# led-cpu.net
KiCad netlist of a schematic drawn in EAGLE
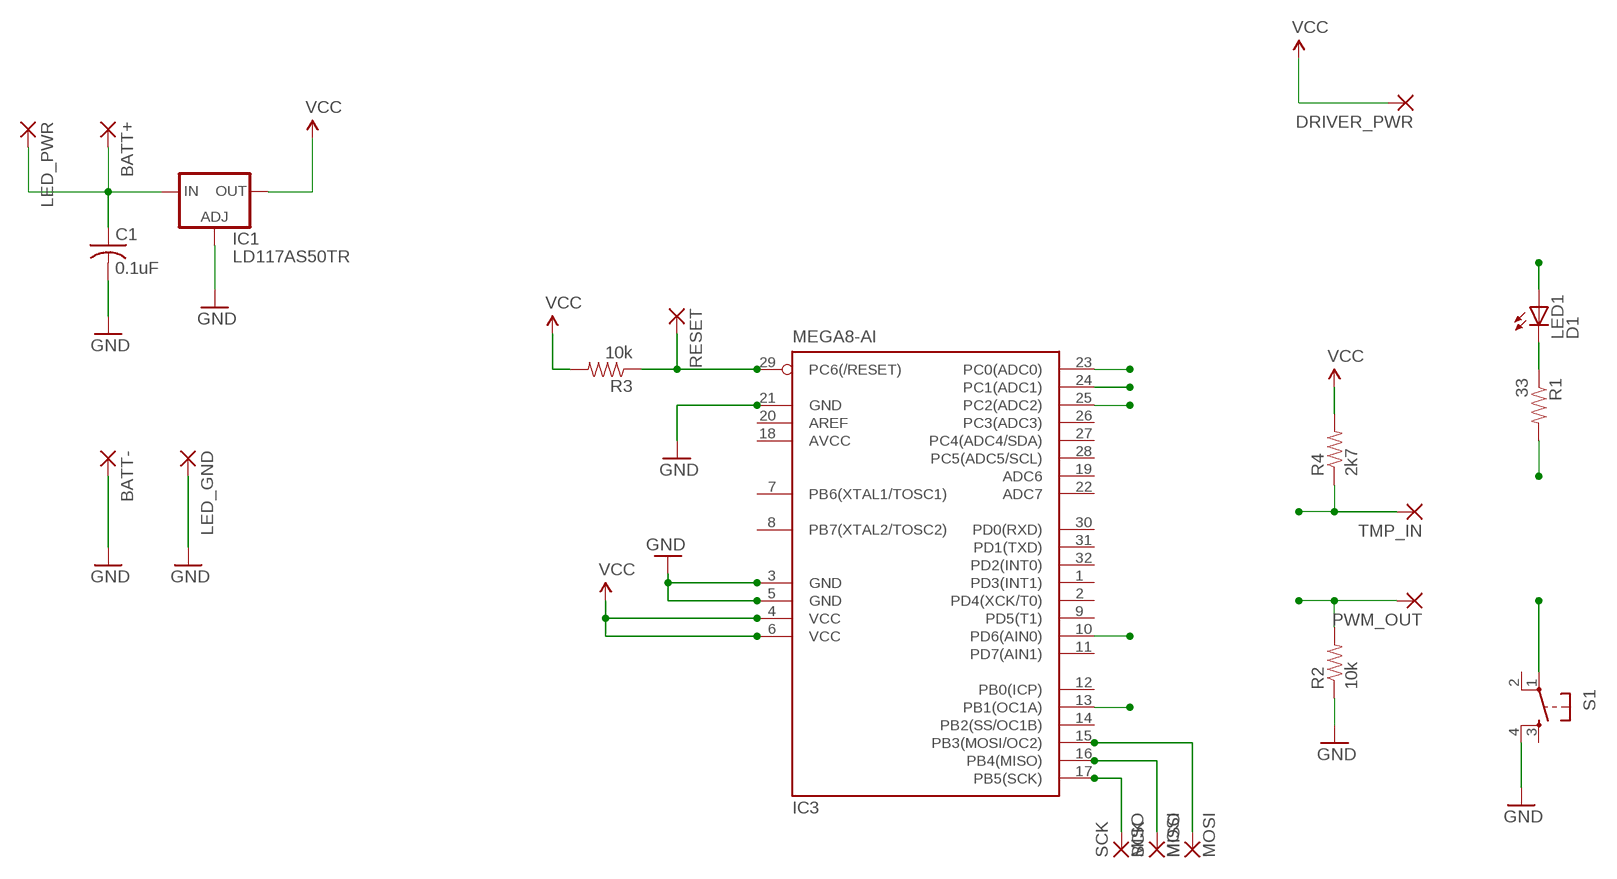
[diagram p0: schematic, sheet 1]

(export (version "E")
  (design (tool "Eeschema 10.0.6"))
  (components
    (comp (ref "BATT+")
      (value "SMD5")
      (footprint "eagle-import:SMD2,54-5,08")
      (libsource (lib "eagle-import") (part "SMD5"))
    )
    (comp (ref "BATT-")
      (value "SMD5")
      (footprint "eagle-import:SMD2,54-5,08")
      (libsource (lib "eagle-import") (part "SMD5"))
    )
    (comp (ref "C1")
      (value "0.1uF")
      (footprint "eagle-import:C0805")
      (libsource (lib "eagle-import") (part "C-USC0805"))
    )
    (comp (ref "DRIVER_PWR")
      (value "WIREPADSMD1,27-254")
      (footprint "eagle-import:SMD1,27-2,54")
      (libsource (lib "eagle-import") (part "WIREPADSMD1,27-254"))
    )
    (comp (ref "IC1")
      (value "LD117AS50TR")
      (footprint "eagle-import:SOT223")
      (libsource (lib "eagle-import") (part "LD117A?S50TR"))
    )
    (comp (ref "IC3")
      (value "MEGA8-AI")
      (footprint "eagle-import:TQFP32-08")
      (fields (field (name "MPN") "ATMEGA8-16AU"))
      (libsource (lib "eagle-import") (part "MEGA8-AI"))
    )
    (comp (ref "LED1")
      (value "D1")
      (footprint "eagle-import:CHIPLED_1206")
      (libsource (lib "eagle-import") (part "LEDCHIPLED_1206"))
    )
    (comp (ref "LED_GND")
      (value "WIREPADSMD1,27-254")
      (footprint "eagle-import:SMD1,27-2,54")
      (libsource (lib "eagle-import") (part "WIREPADSMD1,27-254"))
    )
    (comp (ref "LED_PWR")
      (value "WIREPADSMD1,27-254")
      (footprint "eagle-import:SMD1,27-2,54")
      (libsource (lib "eagle-import") (part "WIREPADSMD1,27-254"))
    )
    (comp (ref "MISO")
      (value "MISO")
      (footprint "eagle-import:SMD1,27-2,54")
      (libsource (lib "eagle-import") (part "SMD2"))
    )
    (comp (ref "MOSI")
      (value "MOSI")
      (footprint "eagle-import:SMD1,27-2,54")
      (libsource (lib "eagle-import") (part "SMD2"))
    )
    (comp (ref "PWM_OUT")
      (value "WIREPADSMD1,27-254")
      (footprint "eagle-import:SMD1,27-2,54")
      (libsource (lib "eagle-import") (part "WIREPADSMD1,27-254"))
    )
    (comp (ref "R1")
      (value "33")
      (footprint "eagle-import:0603-RES")
      (libsource (lib "eagle-import") (part "RESISTOR0603-RES"))
    )
    (comp (ref "R2")
      (value "10k")
      (footprint "eagle-import:0603-RES")
      (libsource (lib "eagle-import") (part "RESISTOR0603-RES"))
    )
    (comp (ref "R3")
      (value "10k")
      (footprint "eagle-import:0603-RES")
      (libsource (lib "eagle-import") (part "RESISTOR0603-RES"))
    )
    (comp (ref "R4")
      (value "2k7")
      (footprint "eagle-import:0603-RES")
      (libsource (lib "eagle-import") (part "RESISTOR0603-RES"))
    )
    (comp (ref "RESET")
      (value "SMD2")
      (footprint "eagle-import:SMD1,27-2,54")
      (libsource (lib "eagle-import") (part "SMD2"))
    )
    (comp (ref "S1")
      (value "TAC_SWITCHPTH")
      (footprint "eagle-import:TACTILE-PTH")
      (libsource (lib "eagle-import") (part "TAC_SWITCHPTH"))
    )
    (comp (ref "SCK")
      (value "SCK")
      (footprint "eagle-import:SMD1,27-2,54")
      (libsource (lib "eagle-import") (part "SMD2"))
    )
    (comp (ref "TMP_IN")
      (value "WIREPADSMD1,27-254")
      (footprint "eagle-import:SMD1,27-2,54")
      (libsource (lib "eagle-import") (part "WIREPADSMD1,27-254"))
    )
  )
  (nets
    (net (code "1") (name "/AVCC") (class "Default")
      (node (ref "IC3") (pin "18") (pinfunction "AVCC_18") (pintype "power_in"))
    )
    (net (code "2") (name "/IND_LED_A") (class "Default")
      (node (ref "IC3") (pin "25") (pinfunction "PC2(ADC2)_25") (pintype "bidirectional"))
      (node (ref "LED1") (pin "A") (pinfunction "A_A") (pintype "passive"))
    )
    (net (code "3") (name "/IND_LED_B") (class "Default")
      (node (ref "IC3") (pin "13") (pinfunction "PB1(OC1A)_13") (pintype "bidirectional"))
      (node (ref "R1") (pin "2") (pinfunction "2_2") (pintype "passive"))
    )
    (net (code "4") (name "/PWM_OUT") (class "Default")
      (node (ref "IC3") (pin "10") (pinfunction "PD6(AIN0)_10") (pintype "bidirectional"))
      (node (ref "PWM_OUT") (pin "1") (pinfunction "P_1") (pintype "passive"))
      (node (ref "R2") (pin "2") (pinfunction "2_2") (pintype "passive"))
    )
    (net (code "5") (name "/PWR_SW") (class "Default")
      (node (ref "IC3") (pin "24") (pinfunction "PC1(ADC1)_24") (pintype "bidirectional"))
      (node (ref "S1") (pin "1") (pinfunction "1_1") (pintype "passive"))
    )
    (net (code "6") (name "/TMP_IN") (class "Default")
      (node (ref "IC3") (pin "23") (pinfunction "PC0(ADC0)_23") (pintype "bidirectional"))
      (node (ref "R4") (pin "1") (pinfunction "1_1") (pintype "passive"))
      (node (ref "TMP_IN") (pin "1") (pinfunction "P_1") (pintype "passive"))
    )
    (net (code "7") (name "GND") (class "Default")
      (node (ref "BATT-") (pin "1") (pinfunction "P_1") (pintype "passive"))
      (node (ref "C1") (pin "2") (pinfunction "2_2") (pintype "passive"))
      (node (ref "IC1") (pin "1") (pinfunction "ADJ_1") (pintype "input"))
      (node (ref "IC3") (pin "21") (pinfunction "GND_21") (pintype "power_in"))
      (node (ref "IC3") (pin "3") (pinfunction "GND_3") (pintype "power_in"))
      (node (ref "IC3") (pin "5") (pinfunction "GND_5") (pintype "power_in"))
      (node (ref "LED_GND") (pin "1") (pinfunction "P_1") (pintype "passive"))
      (node (ref "R2") (pin "1") (pinfunction "1_1") (pintype "passive"))
      (node (ref "S1") (pin "4") (pinfunction "4_4") (pintype "passive"))
    )
    (net (code "8") (name "Net-(BATT+-P)") (class "Default")
      (node (ref "BATT+") (pin "1") (pinfunction "P_1") (pintype "passive"))
      (node (ref "C1") (pin "1") (pinfunction "1_1") (pintype "passive"))
      (node (ref "IC1") (pin "3") (pinfunction "IN_3") (pintype "input"))
      (node (ref "LED_PWR") (pin "1") (pinfunction "P_1") (pintype "passive"))
    )
    (net (code "9") (name "Net-(IC3-PB3(MOSI{slash}OC2))") (class "Default")
      (node (ref "IC3") (pin "15") (pinfunction "PB3(MOSI/OC2)_15") (pintype "bidirectional"))
      (node (ref "MOSI") (pin "1") (pinfunction "P_1") (pintype "passive"))
    )
    (net (code "10") (name "Net-(IC3-PB4(MISO))") (class "Default")
      (node (ref "IC3") (pin "16") (pinfunction "PB4(MISO)_16") (pintype "bidirectional"))
      (node (ref "MISO") (pin "1") (pinfunction "P_1") (pintype "passive"))
    )
    (net (code "11") (name "Net-(IC3-PB5(SCK))") (class "Default")
      (node (ref "IC3") (pin "17") (pinfunction "PB5(SCK)_17") (pintype "bidirectional"))
      (node (ref "SCK") (pin "1") (pinfunction "P_1") (pintype "passive"))
    )
    (net (code "12") (name "Net-(IC3-PC6({slash}RESET))") (class "Default")
      (node (ref "IC3") (pin "29") (pinfunction "PC6(/RESET)_29") (pintype "bidirectional"))
      (node (ref "R3") (pin "1") (pinfunction "1_1") (pintype "passive"))
      (node (ref "RESET") (pin "1") (pinfunction "P_1") (pintype "passive"))
    )
    (net (code "13") (name "Net-(LED1-PadC)") (class "Default")
      (node (ref "LED1") (pin "C") (pinfunction "C_C") (pintype "passive"))
      (node (ref "R1") (pin "1") (pinfunction "1_1") (pintype "passive"))
    )
    (net (code "14") (name "VCC") (class "Default")
      (node (ref "DRIVER_PWR") (pin "1") (pinfunction "P_1") (pintype "passive"))
      (node (ref "IC1") (pin "4") (pinfunction "OUT_4") (pintype "passive"))
      (node (ref "IC3") (pin "4") (pinfunction "VCC_4") (pintype "power_in"))
      (node (ref "IC3") (pin "6") (pinfunction "VCC_6") (pintype "power_in"))
      (node (ref "R3") (pin "2") (pinfunction "2_2") (pintype "passive"))
      (node (ref "R4") (pin "2") (pinfunction "2_2") (pintype "passive"))
    )
    (net (code "15") (name "unconnected-(IC3-ADC6-Pad19)") (class "Default")
      (node (ref "IC3") (pin "19") (pinfunction "ADC6_19") (pintype "bidirectional"))
    )
    (net (code "16") (name "unconnected-(IC3-ADC7-Pad22)") (class "Default")
      (node (ref "IC3") (pin "22") (pinfunction "ADC7_22") (pintype "bidirectional"))
    )
    (net (code "17") (name "unconnected-(IC3-AREF-Pad20)") (class "Default")
      (node (ref "IC3") (pin "20") (pinfunction "AREF_20") (pintype "passive"))
    )
    (net (code "18") (name "unconnected-(IC3-PB0(ICP)-Pad12)") (class "Default")
      (node (ref "IC3") (pin "12") (pinfunction "PB0(ICP)_12") (pintype "bidirectional"))
    )
    (net (code "19") (name "unconnected-(IC3-PB2(SS{slash}OC1B)-Pad14)") (class "Default")
      (node (ref "IC3") (pin "14") (pinfunction "PB2(SS/OC1B)_14") (pintype "bidirectional"))
    )
    (net (code "20") (name "unconnected-(IC3-PB6(XTAL1{slash}TOSC1)-Pad7)") (class "Default")
      (node (ref "IC3") (pin "7") (pinfunction "PB6(XTAL1/TOSC1)_7") (pintype "bidirectional"))
    )
    (net (code "21") (name "unconnected-(IC3-PB7(XTAL2{slash}TOSC2)-Pad8)") (class "Default")
      (node (ref "IC3") (pin "8") (pinfunction "PB7(XTAL2/TOSC2)_8") (pintype "bidirectional"))
    )
    (net (code "22") (name "unconnected-(IC3-PC3(ADC3)-Pad26)") (class "Default")
      (node (ref "IC3") (pin "26") (pinfunction "PC3(ADC3)_26") (pintype "bidirectional"))
    )
    (net (code "23") (name "unconnected-(IC3-PC4(ADC4{slash}SDA)-Pad27)") (class "Default")
      (node (ref "IC3") (pin "27") (pinfunction "PC4(ADC4/SDA)_27") (pintype "bidirectional"))
    )
    (net (code "24") (name "unconnected-(IC3-PC5(ADC5{slash}SCL)-Pad28)") (class "Default")
      (node (ref "IC3") (pin "28") (pinfunction "PC5(ADC5/SCL)_28") (pintype "bidirectional"))
    )
    (net (code "25") (name "unconnected-(IC3-PD0(RXD)-Pad30)") (class "Default")
      (node (ref "IC3") (pin "30") (pinfunction "PD0(RXD)_30") (pintype "bidirectional"))
    )
    (net (code "26") (name "unconnected-(IC3-PD1(TXD)-Pad31)") (class "Default")
      (node (ref "IC3") (pin "31") (pinfunction "PD1(TXD)_31") (pintype "bidirectional"))
    )
    (net (code "27") (name "unconnected-(IC3-PD2(INT0)-Pad32)") (class "Default")
      (node (ref "IC3") (pin "32") (pinfunction "PD2(INT0)_32") (pintype "bidirectional"))
    )
    (net (code "28") (name "unconnected-(IC3-PD3(INT1)-Pad1)") (class "Default")
      (node (ref "IC3") (pin "1") (pinfunction "PD3(INT1)_1") (pintype "bidirectional"))
    )
    (net (code "29") (name "unconnected-(IC3-PD4(XCK{slash}T0)-Pad2)") (class "Default")
      (node (ref "IC3") (pin "2") (pinfunction "PD4(XCK/T0)_2") (pintype "bidirectional"))
    )
    (net (code "30") (name "unconnected-(IC3-PD5(T1)-Pad9)") (class "Default")
      (node (ref "IC3") (pin "9") (pinfunction "PD5(T1)_9") (pintype "bidirectional"))
    )
    (net (code "31") (name "unconnected-(IC3-PD7(AIN1)-Pad11)") (class "Default")
      (node (ref "IC3") (pin "11") (pinfunction "PD7(AIN1)_11") (pintype "bidirectional"))
    )
    (net (code "32") (name "unconnected-(S1-Pad2)") (class "Default")
      (node (ref "S1") (pin "2") (pinfunction "2_2") (pintype "passive"))
    )
    (net (code "33") (name "unconnected-(S1-Pad3)") (class "Default")
      (node (ref "S1") (pin "3") (pinfunction "3_3") (pintype "passive"))
    )
  )
)
